# Sensors.net
KiCad netlist of a schematic drawn in Altium Designer
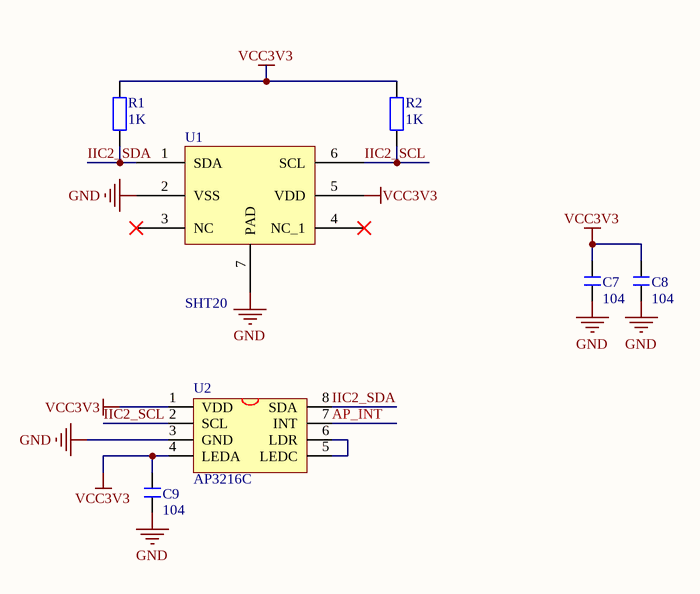
[diagram p0: Sensors.SchDoc]

(export (version "E")
  (design (tool "Eeschema 10.0.6"))
  (components
    (comp (ref "C7")
      (value "104")
      (footprint "C 0603_L")
      (description "无极性贴片电容")
      (fields (field (name "版权归属") "源创客"))
      (libsource (lib "3.1   - 电阻-电容-电感") (part "C"))
    )
    (comp (ref "C8")
      (value "104")
      (footprint "C 0603_L")
      (description "无极性贴片电容")
      (fields (field (name "版权归属") "源创客"))
      (libsource (lib "3.1   - 电阻-电容-电感") (part "C"))
    )
    (comp (ref "C9")
      (value "104")
      (footprint "C 0603_L")
      (description "无极性贴片电容")
      (fields (field (name "版权归属") "源创客"))
      (libsource (lib "3.1   - 电阻-电容-电感") (part "C"))
    )
    (comp (ref "R1")
      (value "1K")
      (footprint "R 0603_L")
      (description "贴片电阻")
      (fields (field (name "版权归属") "源创客"))
      (libsource (lib "3.1   - 电阻-电容-电感") (part "R"))
    )
    (comp (ref "R2")
      (value "1K")
      (footprint "R 0603_L")
      (description "贴片电阻")
      (fields (field (name "版权归属") "源创客"))
      (libsource (lib "3.1   - 电阻-电容-电感") (part "R"))
    )
    (comp (ref "U1") (value "SHT20") (footprint "sht20") (libsource (lib "STM32F103RETX") (part "SHT20")))
    (comp (ref "U2")
      (value "AP3216C")
      (footprint "DFN8")
      (description "ALS+PS Sensor")
      (libsource (lib "MERCURY") (part "AP3216C"))
    )
  )
  (nets
    (net (code "1") (name "/AP_INT") (class "Default")
      (node (ref "U2") (pin "7") (pinfunction "INT_7") (pintype "passive"))
    )
    (net (code "2") (name "/IIC2_SCL") (class "Default")
      (node (ref "R2") (pin "2") (pinfunction "2_2") (pintype "passive"))
      (node (ref "U1") (pin "6") (pinfunction "SCL_6") (pintype "passive"))
      (node (ref "U2") (pin "2") (pinfunction "SCL_2") (pintype "passive"))
    )
    (net (code "3") (name "/IIC2_SDA") (class "Default")
      (node (ref "R1") (pin "2") (pinfunction "2_2") (pintype "passive"))
      (node (ref "U1") (pin "1") (pinfunction "SDA_1") (pintype "passive"))
      (node (ref "U2") (pin "8") (pinfunction "SDA_8") (pintype "passive"))
    )
    (net (code "4") (name "GND") (class "Default")
      (node (ref "C7") (pin "2") (pinfunction "2_2") (pintype "passive"))
      (node (ref "C8") (pin "2") (pinfunction "2_2") (pintype "passive"))
      (node (ref "C9") (pin "2") (pinfunction "2_2") (pintype "passive"))
      (node (ref "U1") (pin "2") (pinfunction "VSS_2") (pintype "passive"))
      (node (ref "U1") (pin "7") (pinfunction "PAD_7") (pintype "passive"))
      (node (ref "U2") (pin "3") (pinfunction "GND_3") (pintype "passive"))
    )
    (net (code "5") (name "Net-(U2-LDR)") (class "Default")
      (node (ref "U2") (pin "5") (pinfunction "LEDC_5") (pintype "passive"))
      (node (ref "U2") (pin "6") (pinfunction "LDR_6") (pintype "passive"))
    )
    (net (code "6") (name "VCC3V3") (class "Default")
      (node (ref "C7") (pin "1") (pinfunction "1_1") (pintype "passive"))
      (node (ref "C8") (pin "1") (pinfunction "1_1") (pintype "passive"))
      (node (ref "C9") (pin "1") (pinfunction "1_1") (pintype "passive"))
      (node (ref "R1") (pin "1") (pinfunction "1_1") (pintype "passive"))
      (node (ref "R2") (pin "1") (pinfunction "1_1") (pintype "passive"))
      (node (ref "U1") (pin "5") (pinfunction "VDD_5") (pintype "passive"))
      (node (ref "U2") (pin "1") (pinfunction "VDD_1") (pintype "passive"))
      (node (ref "U2") (pin "4") (pinfunction "LEDA_4") (pintype "passive"))
    )
    (net (code "7") (name "unconnected-(U1-NC-Pad3)") (class "Default")
      (node (ref "U1") (pin "3") (pinfunction "NC_3") (pintype "passive+no_connect"))
    )
    (net (code "8") (name "unconnected-(U1-NC_1-Pad4)") (class "Default")
      (node (ref "U1") (pin "4") (pinfunction "NC_1_4") (pintype "passive+no_connect"))
    )
  )
)
